# SCH.net
KiCad netlist of a schematic drawn in Altium Designer
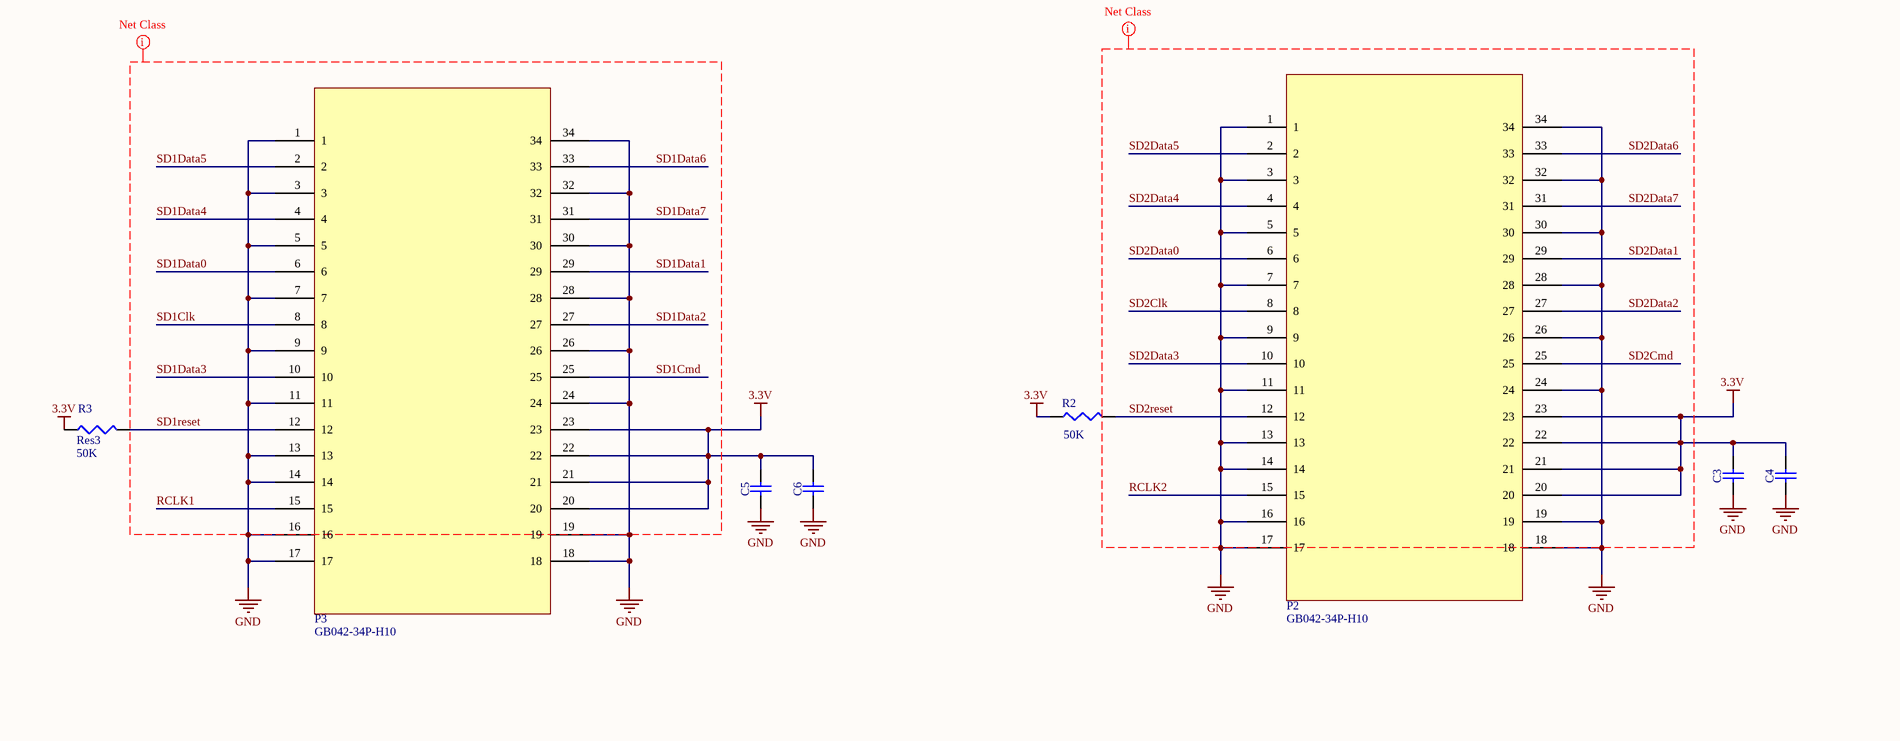
[diagram p0: SCH.SchDoc, top left]
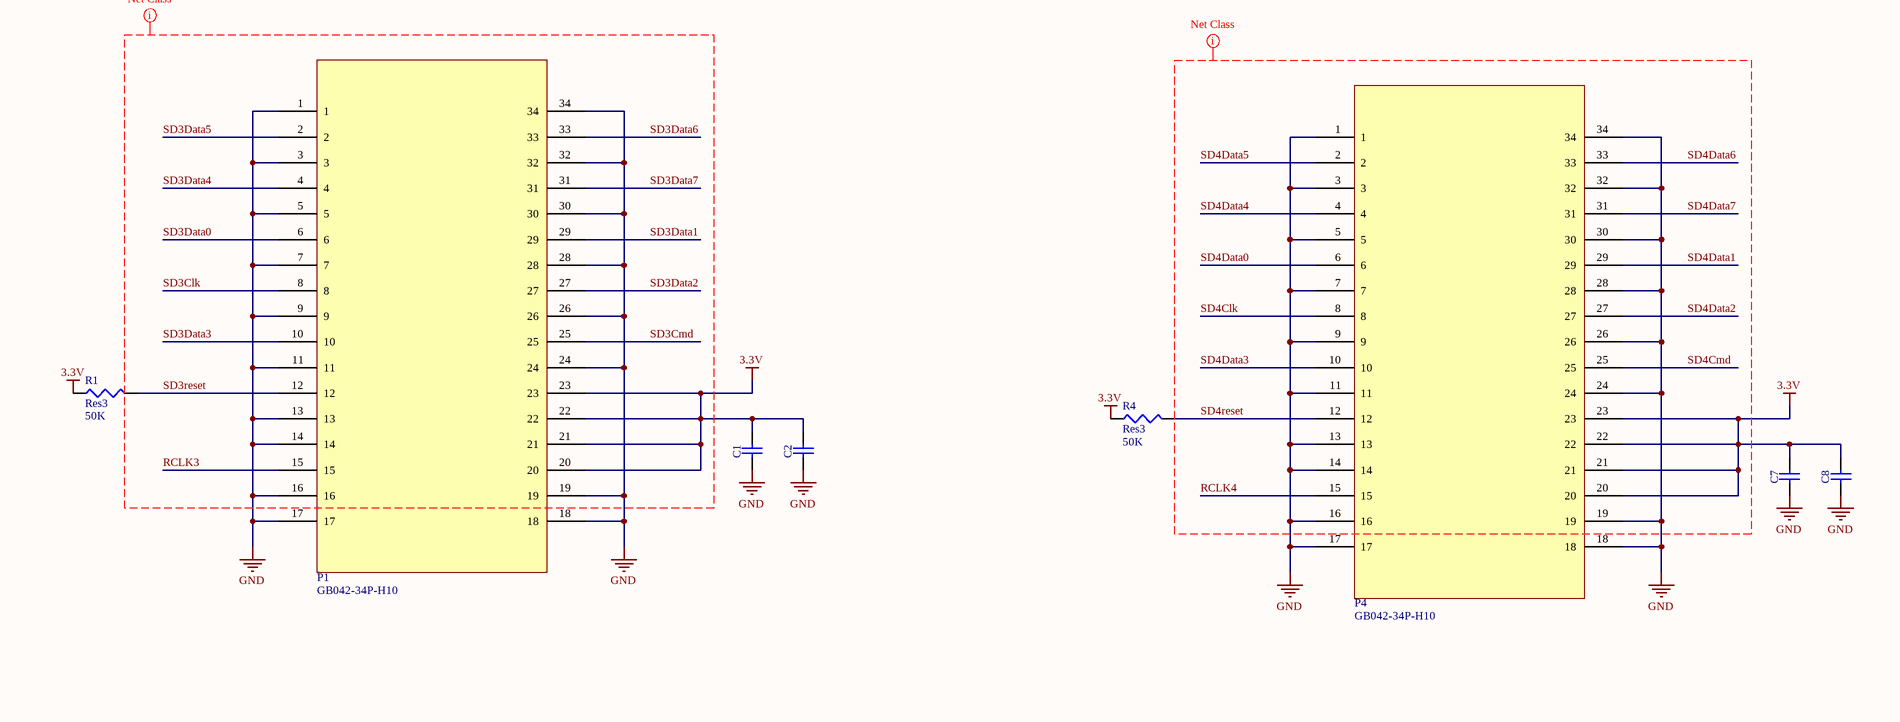
[diagram p1: SCH.SchDoc, top right]
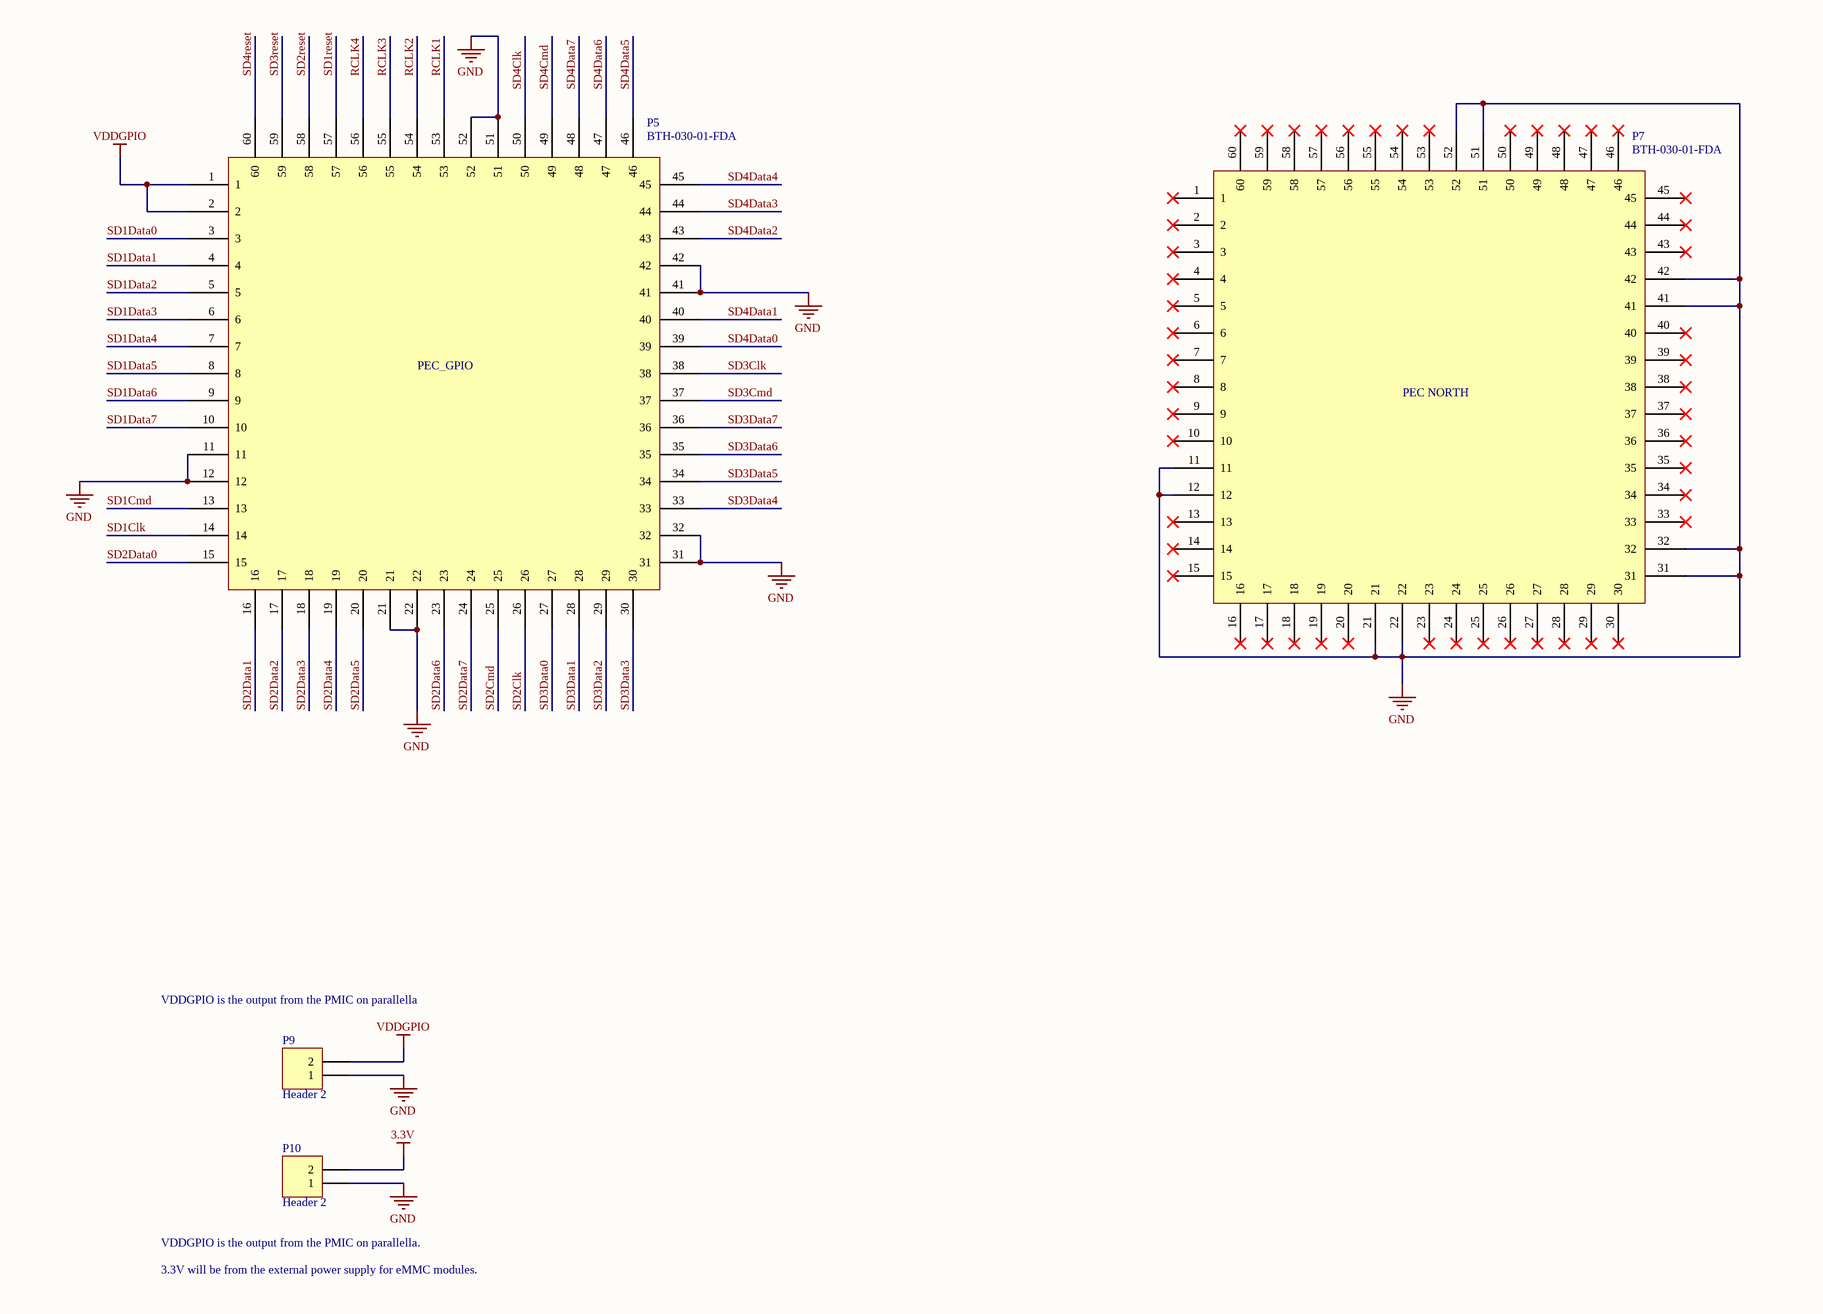
[diagram p2: SCH.SchDoc, bottom left]
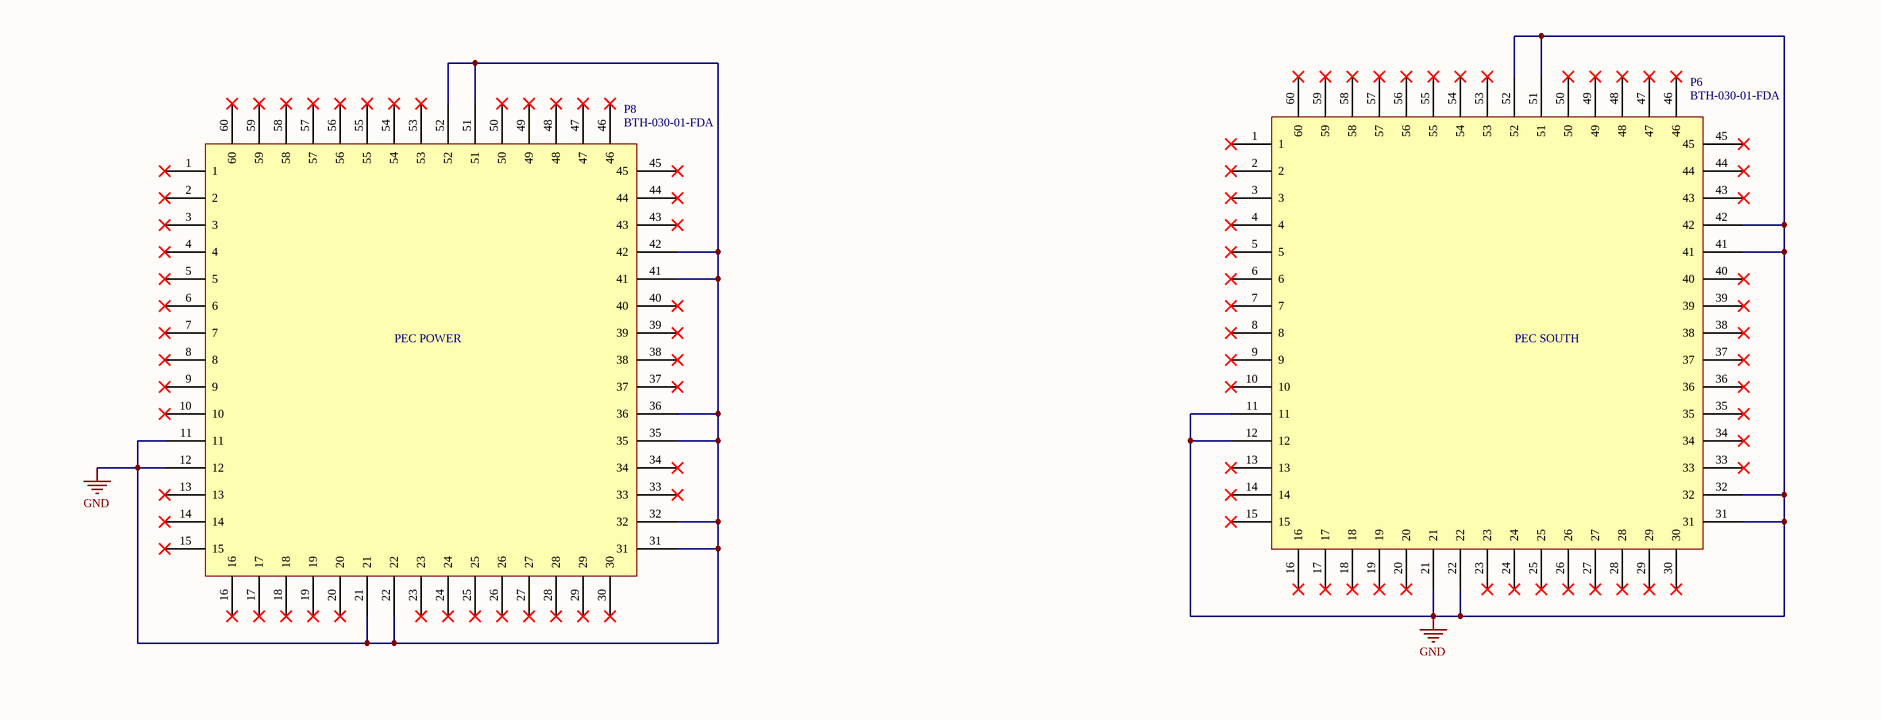
[diagram p3: SCH.SchDoc, bottom right]

(export (version "E")
  (design (tool "Eeschema 10.0.6"))
  (components
    (comp (ref "C1")
      (value "4.7uF")
      (footprint "CAPC3216X140N")
      (description "Non-polarised capacitor")
      (fields
        (field (name "PART NUMBER") "CC1206_4.7UF_16V_10%_X5R")
        (field (name "VOLTAGE") "16V")
        (field (name "AUTHOR") "CERN DEM JLC")
      )
      (libsource (lib "Capacitors") (part "Capacitor - non polarized"))
    )
    (comp (ref "C2")
      (value "100nF")
      (footprint "CAPC1608X87N")
      (description "Non-polarised capacitor")
      (fields
        (field (name "PART NUMBER") "CC0603_100NF_50V_10%_X7R")
        (field (name "VOLTAGE") "50V")
        (field (name "AUTHOR") "CERN DEM JLC")
      )
      (libsource (lib "Capacitors") (part "Capacitor - non polarized"))
    )
    (comp (ref "C3")
      (value "4.7uF")
      (footprint "CAPC3216X140N")
      (description "Non-polarised capacitor")
      (fields
        (field (name "PART NUMBER") "CC1206_4.7UF_16V_10%_X5R")
        (field (name "VOLTAGE") "16V")
        (field (name "AUTHOR") "CERN DEM JLC")
      )
      (libsource (lib "Capacitors") (part "Capacitor - non polarized"))
    )
    (comp (ref "C4")
      (value "100nF")
      (footprint "CAPC1608X87N")
      (description "Non-polarised capacitor")
      (fields
        (field (name "PART NUMBER") "CC0603_100NF_50V_10%_X7R")
        (field (name "VOLTAGE") "50V")
        (field (name "AUTHOR") "CERN DEM JLC")
      )
      (libsource (lib "Capacitors") (part "Capacitor - non polarized"))
    )
    (comp (ref "C5")
      (value "4.7uF")
      (footprint "CAPC3216X140N")
      (description "Non-polarised capacitor")
      (fields
        (field (name "PART NUMBER") "CC1206_4.7UF_16V_10%_X5R")
        (field (name "VOLTAGE") "16V")
        (field (name "AUTHOR") "CERN DEM JLC")
      )
      (libsource (lib "Capacitors") (part "Capacitor - non polarized"))
    )
    (comp (ref "C6")
      (value "100nF")
      (footprint "CAPC1608X87N")
      (description "Non-polarised capacitor")
      (fields
        (field (name "PART NUMBER") "CC0603_100NF_50V_10%_X7R")
        (field (name "VOLTAGE") "50V")
        (field (name "AUTHOR") "CERN DEM JLC")
      )
      (libsource (lib "Capacitors") (part "Capacitor - non polarized"))
    )
    (comp (ref "C7")
      (value "4.7uF")
      (footprint "CAPC3216X140N")
      (description "Non-polarised capacitor")
      (fields
        (field (name "PART NUMBER") "CC1206_4.7UF_16V_10%_X5R")
        (field (name "VOLTAGE") "16V")
        (field (name "AUTHOR") "CERN DEM JLC")
      )
      (libsource (lib "Capacitors") (part "Capacitor - non polarized"))
    )
    (comp (ref "C8")
      (value "100nF")
      (footprint "CAPC1608X87N")
      (description "Non-polarised capacitor")
      (fields
        (field (name "PART NUMBER") "CC0603_100NF_50V_10%_X7R")
        (field (name "VOLTAGE") "50V")
        (field (name "AUTHOR") "CERN DEM JLC")
      )
      (libsource (lib "Capacitors") (part "Capacitor - non polarized"))
    )
    (comp (ref "P1")
      (value "GB042-34P-H10")
      (footprint "GB042-34P-H10")
      (libsource (lib "Schlib1") (part "GB042-34P-H10"))
    )
    (comp (ref "P2")
      (value "GB042-34P-H10")
      (footprint "GB042-34P-H10")
      (libsource (lib "Schlib1") (part "GB042-34P-H10"))
    )
    (comp (ref "P3")
      (value "GB042-34P-H10")
      (footprint "GB042-34P-H10")
      (libsource (lib "Schlib1") (part "GB042-34P-H10"))
    )
    (comp (ref "P4")
      (value "GB042-34P-H10")
      (footprint "GB042-34P-H10")
      (libsource (lib "Schlib1") (part "GB042-34P-H10"))
    )
    (comp (ref "P5")
      (value "BTH-030-01-FDA")
      (footprint "BTH-030-01-F-D-A")
      (libsource (lib "Schlib1") (part "BTH-030-01-FDA"))
    )
    (comp (ref "P6")
      (value "BTH-030-01-FDA")
      (footprint "BTH-030-01-F-D-A")
      (libsource (lib "Schlib1") (part "BTH-030-01-FDA"))
    )
    (comp (ref "P7")
      (value "BTH-030-01-FDA")
      (footprint "BTH-030-01-F-D-A")
      (libsource (lib "Schlib1") (part "BTH-030-01-FDA"))
    )
    (comp (ref "P8")
      (value "BTH-030-01-FDA")
      (footprint "BTH-030-01-F-D-A")
      (libsource (lib "Schlib1") (part "BTH-030-01-FDA"))
    )
    (comp (ref "P9")
      (value "Header 2")
      (footprint "HDR1X2")
      (description "Header, 2-Pin")
      (fields (field (name "PUBLISHER") "Altium Limited"))
      (libsource (lib "Miscellaneous Connectors") (part "Header 2"))
    )
    (comp (ref "P10")
      (value "Header 2")
      (footprint "HDR1X2")
      (description "Header, 2-Pin")
      (fields (field (name "PUBLISHER") "Altium Limited"))
      (libsource (lib "Miscellaneous Connectors") (part "Header 2"))
    )
    (comp (ref "R1")
      (value "Res3")
      (footprint "J1-0603")
      (description "Resistor")
      (fields (field (name "ALTIUM_VALUE") "50K") (field (name "PUBLISHER") "Altium Limited"))
      (libsource (lib "Miscellaneous Devices") (part "Res3"))
    )
    (comp (ref "R2")
      (value "50K")
      (footprint "J1-0603")
      (description "Resistor")
      (fields (field (name "Comment") "Res3") (field (name "PUBLISHER") "Altium Limited"))
      (libsource (lib "Miscellaneous Devices") (part "Res3"))
    )
    (comp (ref "R3")
      (value "Res3")
      (footprint "J1-0603")
      (description "Resistor")
      (fields (field (name "ALTIUM_VALUE") "50K") (field (name "PUBLISHER") "Altium Limited"))
      (libsource (lib "Miscellaneous Devices") (part "Res3"))
    )
    (comp (ref "R4")
      (value "Res3")
      (footprint "J1-0603")
      (description "Resistor")
      (fields (field (name "ALTIUM_VALUE") "50K") (field (name "PUBLISHER") "Altium Limited"))
      (libsource (lib "Miscellaneous Devices") (part "Res3"))
    )
  )
  (nets
    (net (code "1") (name "/RCLK1") (class "Default")
      (node (ref "P3") (pin "15") (pinfunction "15_15") (pintype "passive"))
      (node (ref "P5") (pin "53") (pinfunction "53_53") (pintype "passive"))
    )
    (net (code "2") (name "/RCLK2") (class "Default")
      (node (ref "P2") (pin "15") (pinfunction "15_15") (pintype "passive"))
      (node (ref "P5") (pin "54") (pinfunction "54_54") (pintype "passive"))
    )
    (net (code "3") (name "/RCLK3") (class "Default")
      (node (ref "P1") (pin "15") (pinfunction "15_15") (pintype "passive"))
      (node (ref "P5") (pin "55") (pinfunction "55_55") (pintype "passive"))
    )
    (net (code "4") (name "/RCLK4") (class "Default")
      (node (ref "P4") (pin "15") (pinfunction "15_15") (pintype "passive"))
      (node (ref "P5") (pin "56") (pinfunction "56_56") (pintype "passive"))
    )
    (net (code "5") (name "/SD1Clk") (class "Default")
      (node (ref "P3") (pin "8") (pinfunction "8_8") (pintype "passive"))
      (node (ref "P5") (pin "14") (pinfunction "14_14") (pintype "passive"))
    )
    (net (code "6") (name "/SD1Cmd") (class "Default")
      (node (ref "P3") (pin "25") (pinfunction "25_25") (pintype "passive"))
      (node (ref "P5") (pin "13") (pinfunction "13_13") (pintype "passive"))
    )
    (net (code "7") (name "/SD1Data0") (class "Default")
      (node (ref "P3") (pin "6") (pinfunction "6_6") (pintype "passive"))
      (node (ref "P5") (pin "3") (pinfunction "3_3") (pintype "passive"))
    )
    (net (code "8") (name "/SD1Data1") (class "Default")
      (node (ref "P3") (pin "29") (pinfunction "29_29") (pintype "passive"))
      (node (ref "P5") (pin "4") (pinfunction "4_4") (pintype "passive"))
    )
    (net (code "9") (name "/SD1Data2") (class "Default")
      (node (ref "P3") (pin "27") (pinfunction "27_27") (pintype "passive"))
      (node (ref "P5") (pin "5") (pinfunction "5_5") (pintype "passive"))
    )
    (net (code "10") (name "/SD1Data3") (class "Default")
      (node (ref "P3") (pin "10") (pinfunction "10_10") (pintype "passive"))
      (node (ref "P5") (pin "6") (pinfunction "6_6") (pintype "passive"))
    )
    (net (code "11") (name "/SD1Data4") (class "Default")
      (node (ref "P3") (pin "4") (pinfunction "4_4") (pintype "passive"))
      (node (ref "P5") (pin "7") (pinfunction "7_7") (pintype "passive"))
    )
    (net (code "12") (name "/SD1Data5") (class "Default")
      (node (ref "P3") (pin "2") (pinfunction "2_2") (pintype "passive"))
      (node (ref "P5") (pin "8") (pinfunction "8_8") (pintype "passive"))
    )
    (net (code "13") (name "/SD1Data6") (class "Default")
      (node (ref "P3") (pin "33") (pinfunction "33_33") (pintype "passive"))
      (node (ref "P5") (pin "9") (pinfunction "9_9") (pintype "passive"))
    )
    (net (code "14") (name "/SD1Data7") (class "Default")
      (node (ref "P3") (pin "31") (pinfunction "31_31") (pintype "passive"))
      (node (ref "P5") (pin "10") (pinfunction "10_10") (pintype "passive"))
    )
    (net (code "15") (name "/SD1reset") (class "Default")
      (node (ref "P3") (pin "12") (pinfunction "12_12") (pintype "passive"))
      (node (ref "P5") (pin "57") (pinfunction "57_57") (pintype "passive"))
      (node (ref "R3") (pin "2") (pinfunction "2_2") (pintype "passive"))
    )
    (net (code "16") (name "/SD2Clk") (class "Default")
      (node (ref "P2") (pin "8") (pinfunction "8_8") (pintype "passive"))
      (node (ref "P5") (pin "26") (pinfunction "26_26") (pintype "passive"))
    )
    (net (code "17") (name "/SD2Cmd") (class "Default")
      (node (ref "P2") (pin "25") (pinfunction "25_25") (pintype "passive"))
      (node (ref "P5") (pin "25") (pinfunction "25_25") (pintype "passive"))
    )
    (net (code "18") (name "/SD2Data0") (class "Default")
      (node (ref "P2") (pin "6") (pinfunction "6_6") (pintype "passive"))
      (node (ref "P5") (pin "15") (pinfunction "15_15") (pintype "passive"))
    )
    (net (code "19") (name "/SD2Data1") (class "Default")
      (node (ref "P2") (pin "29") (pinfunction "29_29") (pintype "passive"))
      (node (ref "P5") (pin "16") (pinfunction "16_16") (pintype "passive"))
    )
    (net (code "20") (name "/SD2Data2") (class "Default")
      (node (ref "P2") (pin "27") (pinfunction "27_27") (pintype "passive"))
      (node (ref "P5") (pin "17") (pinfunction "17_17") (pintype "passive"))
    )
    (net (code "21") (name "/SD2Data3") (class "Default")
      (node (ref "P2") (pin "10") (pinfunction "10_10") (pintype "passive"))
      (node (ref "P5") (pin "18") (pinfunction "18_18") (pintype "passive"))
    )
    (net (code "22") (name "/SD2Data4") (class "Default")
      (node (ref "P2") (pin "4") (pinfunction "4_4") (pintype "passive"))
      (node (ref "P5") (pin "19") (pinfunction "19_19") (pintype "passive"))
    )
    (net (code "23") (name "/SD2Data5") (class "Default")
      (node (ref "P2") (pin "2") (pinfunction "2_2") (pintype "passive"))
      (node (ref "P5") (pin "20") (pinfunction "20_20") (pintype "passive"))
    )
    (net (code "24") (name "/SD2Data6") (class "Default")
      (node (ref "P2") (pin "33") (pinfunction "33_33") (pintype "passive"))
      (node (ref "P5") (pin "23") (pinfunction "23_23") (pintype "passive"))
    )
    (net (code "25") (name "/SD2Data7") (class "Default")
      (node (ref "P2") (pin "31") (pinfunction "31_31") (pintype "passive"))
      (node (ref "P5") (pin "24") (pinfunction "24_24") (pintype "passive"))
    )
    (net (code "26") (name "/SD2reset") (class "Default")
      (node (ref "P2") (pin "12") (pinfunction "12_12") (pintype "passive"))
      (node (ref "P5") (pin "58") (pinfunction "58_58") (pintype "passive"))
      (node (ref "R2") (pin "2") (pinfunction "2_2") (pintype "passive"))
    )
    (net (code "27") (name "/SD3Clk") (class "Default")
      (node (ref "P1") (pin "8") (pinfunction "8_8") (pintype "passive"))
      (node (ref "P5") (pin "38") (pinfunction "38_38") (pintype "passive"))
    )
    (net (code "28") (name "/SD3Cmd") (class "Default")
      (node (ref "P1") (pin "25") (pinfunction "25_25") (pintype "passive"))
      (node (ref "P5") (pin "37") (pinfunction "37_37") (pintype "passive"))
    )
    (net (code "29") (name "/SD3Data0") (class "Default")
      (node (ref "P1") (pin "6") (pinfunction "6_6") (pintype "passive"))
      (node (ref "P5") (pin "27") (pinfunction "27_27") (pintype "passive"))
    )
    (net (code "30") (name "/SD3Data1") (class "Default")
      (node (ref "P1") (pin "29") (pinfunction "29_29") (pintype "passive"))
      (node (ref "P5") (pin "28") (pinfunction "28_28") (pintype "passive"))
    )
    (net (code "31") (name "/SD3Data2") (class "Default")
      (node (ref "P1") (pin "27") (pinfunction "27_27") (pintype "passive"))
      (node (ref "P5") (pin "29") (pinfunction "29_29") (pintype "passive"))
    )
    (net (code "32") (name "/SD3Data3") (class "Default")
      (node (ref "P1") (pin "10") (pinfunction "10_10") (pintype "passive"))
      (node (ref "P5") (pin "30") (pinfunction "30_30") (pintype "passive"))
    )
    (net (code "33") (name "/SD3Data4") (class "Default")
      (node (ref "P1") (pin "4") (pinfunction "4_4") (pintype "passive"))
      (node (ref "P5") (pin "33") (pinfunction "33_33") (pintype "passive"))
    )
    (net (code "34") (name "/SD3Data5") (class "Default")
      (node (ref "P1") (pin "2") (pinfunction "2_2") (pintype "passive"))
      (node (ref "P5") (pin "34") (pinfunction "34_34") (pintype "passive"))
    )
    (net (code "35") (name "/SD3Data6") (class "Default")
      (node (ref "P1") (pin "33") (pinfunction "33_33") (pintype "passive"))
      (node (ref "P5") (pin "35") (pinfunction "35_35") (pintype "passive"))
    )
    (net (code "36") (name "/SD3Data7") (class "Default")
      (node (ref "P1") (pin "31") (pinfunction "31_31") (pintype "passive"))
      (node (ref "P5") (pin "36") (pinfunction "36_36") (pintype "passive"))
    )
    (net (code "37") (name "/SD3reset") (class "Default")
      (node (ref "P1") (pin "12") (pinfunction "12_12") (pintype "passive"))
      (node (ref "P5") (pin "59") (pinfunction "59_59") (pintype "passive"))
      (node (ref "R1") (pin "2") (pinfunction "2_2") (pintype "passive"))
    )
    (net (code "38") (name "/SD4Clk") (class "Default")
      (node (ref "P4") (pin "8") (pinfunction "8_8") (pintype "passive"))
      (node (ref "P5") (pin "50") (pinfunction "50_50") (pintype "passive"))
    )
    (net (code "39") (name "/SD4Cmd") (class "Default")
      (node (ref "P4") (pin "25") (pinfunction "25_25") (pintype "passive"))
      (node (ref "P5") (pin "49") (pinfunction "49_49") (pintype "passive"))
    )
    (net (code "40") (name "/SD4Data0") (class "Default")
      (node (ref "P4") (pin "6") (pinfunction "6_6") (pintype "passive"))
      (node (ref "P5") (pin "39") (pinfunction "39_39") (pintype "passive"))
    )
    (net (code "41") (name "/SD4Data1") (class "Default")
      (node (ref "P4") (pin "29") (pinfunction "29_29") (pintype "passive"))
      (node (ref "P5") (pin "40") (pinfunction "40_40") (pintype "passive"))
    )
    (net (code "42") (name "/SD4Data2") (class "Default")
      (node (ref "P4") (pin "27") (pinfunction "27_27") (pintype "passive"))
      (node (ref "P5") (pin "43") (pinfunction "43_43") (pintype "passive"))
    )
    (net (code "43") (name "/SD4Data3") (class "Default")
      (node (ref "P4") (pin "10") (pinfunction "10_10") (pintype "passive"))
      (node (ref "P5") (pin "44") (pinfunction "44_44") (pintype "passive"))
    )
    (net (code "44") (name "/SD4Data4") (class "Default")
      (node (ref "P4") (pin "4") (pinfunction "4_4") (pintype "passive"))
      (node (ref "P5") (pin "45") (pinfunction "45_45") (pintype "passive"))
    )
    (net (code "45") (name "/SD4Data5") (class "Default")
      (node (ref "P4") (pin "2") (pinfunction "2_2") (pintype "passive"))
      (node (ref "P5") (pin "46") (pinfunction "46_46") (pintype "passive"))
    )
    (net (code "46") (name "/SD4Data6") (class "Default")
      (node (ref "P4") (pin "33") (pinfunction "33_33") (pintype "passive"))
      (node (ref "P5") (pin "47") (pinfunction "47_47") (pintype "passive"))
    )
    (net (code "47") (name "/SD4Data7") (class "Default")
      (node (ref "P4") (pin "31") (pinfunction "31_31") (pintype "passive"))
      (node (ref "P5") (pin "48") (pinfunction "48_48") (pintype "passive"))
    )
    (net (code "48") (name "/SD4reset") (class "Default")
      (node (ref "P4") (pin "12") (pinfunction "12_12") (pintype "passive"))
      (node (ref "P5") (pin "60") (pinfunction "60_60") (pintype "passive"))
      (node (ref "R4") (pin "2") (pinfunction "2_2") (pintype "passive"))
    )
    (net (code "49") (name "3.3V") (class "Default")
      (node (ref "C1") (pin "2") (pinfunction "2_2") (pintype "passive"))
      (node (ref "C2") (pin "2") (pinfunction "2_2") (pintype "passive"))
      (node (ref "C3") (pin "2") (pinfunction "2_2") (pintype "passive"))
      (node (ref "C4") (pin "2") (pinfunction "2_2") (pintype "passive"))
      (node (ref "C5") (pin "2") (pinfunction "2_2") (pintype "passive"))
      (node (ref "C6") (pin "2") (pinfunction "2_2") (pintype "passive"))
      (node (ref "C7") (pin "2") (pinfunction "2_2") (pintype "passive"))
      (node (ref "C8") (pin "2") (pinfunction "2_2") (pintype "passive"))
      (node (ref "P1") (pin "20") (pinfunction "20_20") (pintype "passive"))
      (node (ref "P1") (pin "21") (pinfunction "21_21") (pintype "passive"))
      (node (ref "P1") (pin "22") (pinfunction "22_22") (pintype "passive"))
      (node (ref "P1") (pin "23") (pinfunction "23_23") (pintype "passive"))
      (node (ref "P10") (pin "2") (pinfunction "2_2") (pintype "passive"))
      (node (ref "P2") (pin "20") (pinfunction "20_20") (pintype "passive"))
      (node (ref "P2") (pin "21") (pinfunction "21_21") (pintype "passive"))
      (node (ref "P2") (pin "22") (pinfunction "22_22") (pintype "passive"))
      (node (ref "P2") (pin "23") (pinfunction "23_23") (pintype "passive"))
      (node (ref "P3") (pin "20") (pinfunction "20_20") (pintype "passive"))
      (node (ref "P3") (pin "21") (pinfunction "21_21") (pintype "passive"))
      (node (ref "P3") (pin "22") (pinfunction "22_22") (pintype "passive"))
      (node (ref "P3") (pin "23") (pinfunction "23_23") (pintype "passive"))
      (node (ref "P4") (pin "20") (pinfunction "20_20") (pintype "passive"))
      (node (ref "P4") (pin "21") (pinfunction "21_21") (pintype "passive"))
      (node (ref "P4") (pin "22") (pinfunction "22_22") (pintype "passive"))
      (node (ref "P4") (pin "23") (pinfunction "23_23") (pintype "passive"))
      (node (ref "R1") (pin "1") (pinfunction "1_1") (pintype "passive"))
      (node (ref "R2") (pin "1") (pinfunction "1_1") (pintype "passive"))
      (node (ref "R3") (pin "1") (pinfunction "1_1") (pintype "passive"))
      (node (ref "R4") (pin "1") (pinfunction "1_1") (pintype "passive"))
    )
    (net (code "50") (name "GND") (class "Default")
      (node (ref "C1") (pin "1") (pinfunction "1_1") (pintype "passive"))
      (node (ref "C2") (pin "1") (pinfunction "1_1") (pintype "passive"))
      (node (ref "C3") (pin "1") (pinfunction "1_1") (pintype "passive"))
      (node (ref "C4") (pin "1") (pinfunction "1_1") (pintype "passive"))
      (node (ref "C5") (pin "1") (pinfunction "1_1") (pintype "passive"))
      (node (ref "C6") (pin "1") (pinfunction "1_1") (pintype "passive"))
      (node (ref "C7") (pin "1") (pinfunction "1_1") (pintype "passive"))
      (node (ref "C8") (pin "1") (pinfunction "1_1") (pintype "passive"))
      (node (ref "P1") (pin "1") (pinfunction "1_1") (pintype "passive"))
      (node (ref "P1") (pin "11") (pinfunction "11_11") (pintype "passive"))
      (node (ref "P1") (pin "13") (pinfunction "13_13") (pintype "passive"))
      (node (ref "P1") (pin "14") (pinfunction "14_14") (pintype "passive"))
      (node (ref "P1") (pin "16") (pinfunction "16_16") (pintype "passive"))
      (node (ref "P1") (pin "17") (pinfunction "17_17") (pintype "passive"))
      (node (ref "P1") (pin "18") (pinfunction "18_18") (pintype "passive"))
      (node (ref "P1") (pin "19") (pinfunction "19_19") (pintype "passive"))
      (node (ref "P1") (pin "24") (pinfunction "24_24") (pintype "passive"))
      (node (ref "P1") (pin "26") (pinfunction "26_26") (pintype "passive"))
      (node (ref "P1") (pin "28") (pinfunction "28_28") (pintype "passive"))
      (node (ref "P1") (pin "3") (pinfunction "3_3") (pintype "passive"))
      (node (ref "P1") (pin "30") (pinfunction "30_30") (pintype "passive"))
      (node (ref "P1") (pin "32") (pinfunction "32_32") (pintype "passive"))
      (node (ref "P1") (pin "34") (pinfunction "34_34") (pintype "passive"))
      (node (ref "P1") (pin "5") (pinfunction "5_5") (pintype "passive"))
      (node (ref "P1") (pin "7") (pinfunction "7_7") (pintype "passive"))
      (node (ref "P1") (pin "9") (pinfunction "9_9") (pintype "passive"))
      (node (ref "P10") (pin "1") (pinfunction "1_1") (pintype "passive"))
      (node (ref "P2") (pin "1") (pinfunction "1_1") (pintype "passive"))
      (node (ref "P2") (pin "11") (pinfunction "11_11") (pintype "passive"))
      (node (ref "P2") (pin "13") (pinfunction "13_13") (pintype "passive"))
      (node (ref "P2") (pin "14") (pinfunction "14_14") (pintype "passive"))
      (node (ref "P2") (pin "16") (pinfunction "16_16") (pintype "passive"))
      (node (ref "P2") (pin "17") (pinfunction "17_17") (pintype "passive"))
      (node (ref "P2") (pin "18") (pinfunction "18_18") (pintype "passive"))
      (node (ref "P2") (pin "19") (pinfunction "19_19") (pintype "passive"))
      (node (ref "P2") (pin "24") (pinfunction "24_24") (pintype "passive"))
      (node (ref "P2") (pin "26") (pinfunction "26_26") (pintype "passive"))
      (node (ref "P2") (pin "28") (pinfunction "28_28") (pintype "passive"))
      (node (ref "P2") (pin "3") (pinfunction "3_3") (pintype "passive"))
      (node (ref "P2") (pin "30") (pinfunction "30_30") (pintype "passive"))
      (node (ref "P2") (pin "32") (pinfunction "32_32") (pintype "passive"))
      (node (ref "P2") (pin "34") (pinfunction "34_34") (pintype "passive"))
      (node (ref "P2") (pin "5") (pinfunction "5_5") (pintype "passive"))
      (node (ref "P2") (pin "7") (pinfunction "7_7") (pintype "passive"))
      (node (ref "P2") (pin "9") (pinfunction "9_9") (pintype "passive"))
      (node (ref "P3") (pin "1") (pinfunction "1_1") (pintype "passive"))
      (node (ref "P3") (pin "11") (pinfunction "11_11") (pintype "passive"))
      (node (ref "P3") (pin "13") (pinfunction "13_13") (pintype "passive"))
      (node (ref "P3") (pin "14") (pinfunction "14_14") (pintype "passive"))
      (node (ref "P3") (pin "16") (pinfunction "16_16") (pintype "passive"))
      (node (ref "P3") (pin "17") (pinfunction "17_17") (pintype "passive"))
      (node (ref "P3") (pin "18") (pinfunction "18_18") (pintype "passive"))
      (node (ref "P3") (pin "19") (pinfunction "19_19") (pintype "passive"))
      (node (ref "P3") (pin "24") (pinfunction "24_24") (pintype "passive"))
      (node (ref "P3") (pin "26") (pinfunction "26_26") (pintype "passive"))
      (node (ref "P3") (pin "28") (pinfunction "28_28") (pintype "passive"))
      (node (ref "P3") (pin "3") (pinfunction "3_3") (pintype "passive"))
      (node (ref "P3") (pin "30") (pinfunction "30_30") (pintype "passive"))
      (node (ref "P3") (pin "32") (pinfunction "32_32") (pintype "passive"))
      (node (ref "P3") (pin "34") (pinfunction "34_34") (pintype "passive"))
      (node (ref "P3") (pin "5") (pinfunction "5_5") (pintype "passive"))
      (node (ref "P3") (pin "7") (pinfunction "7_7") (pintype "passive"))
      (node (ref "P3") (pin "9") (pinfunction "9_9") (pintype "passive"))
      (node (ref "P4") (pin "1") (pinfunction "1_1") (pintype "passive"))
      (node (ref "P4") (pin "11") (pinfunction "11_11") (pintype "passive"))
      (node (ref "P4") (pin "13") (pinfunction "13_13") (pintype "passive"))
      (node (ref "P4") (pin "14") (pinfunction "14_14") (pintype "passive"))
      (node (ref "P4") (pin "16") (pinfunction "16_16") (pintype "passive"))
      (node (ref "P4") (pin "17") (pinfunction "17_17") (pintype "passive"))
      (node (ref "P4") (pin "18") (pinfunction "18_18") (pintype "passive"))
      (node (ref "P4") (pin "19") (pinfunction "19_19") (pintype "passive"))
      (node (ref "P4") (pin "24") (pinfunction "24_24") (pintype "passive"))
      (node (ref "P4") (pin "26") (pinfunction "26_26") (pintype "passive"))
      (node (ref "P4") (pin "28") (pinfunction "28_28") (pintype "passive"))
      (node (ref "P4") (pin "3") (pinfunction "3_3") (pintype "passive"))
      (node (ref "P4") (pin "30") (pinfunction "30_30") (pintype "passive"))
      (node (ref "P4") (pin "32") (pinfunction "32_32") (pintype "passive"))
      (node (ref "P4") (pin "34") (pinfunction "34_34") (pintype "passive"))
      (node (ref "P4") (pin "5") (pinfunction "5_5") (pintype "passive"))
      (node (ref "P4") (pin "7") (pinfunction "7_7") (pintype "passive"))
      (node (ref "P4") (pin "9") (pinfunction "9_9") (pintype "passive"))
      (node (ref "P5") (pin "11") (pinfunction "11_11") (pintype "passive"))
      (node (ref "P5") (pin "12") (pinfunction "12_12") (pintype "passive"))
      (node (ref "P5") (pin "21") (pinfunction "21_21") (pintype "passive"))
      (node (ref "P5") (pin "22") (pinfunction "22_22") (pintype "passive"))
      (node (ref "P5") (pin "31") (pinfunction "31_31") (pintype "passive"))
      (node (ref "P5") (pin "32") (pinfunction "32_32") (pintype "passive"))
      (node (ref "P5") (pin "41") (pinfunction "41_41") (pintype "passive"))
      (node (ref "P5") (pin "42") (pinfunction "42_42") (pintype "passive"))
      (node (ref "P5") (pin "51") (pinfunction "51_51") (pintype "passive"))
      (node (ref "P5") (pin "52") (pinfunction "52_52") (pintype "passive"))
      (node (ref "P6") (pin "11") (pinfunction "11_11") (pintype "passive"))
      (node (ref "P6") (pin "12") (pinfunction "12_12") (pintype "passive"))
      (node (ref "P6") (pin "21") (pinfunction "21_21") (pintype "passive"))
      (node (ref "P6") (pin "22") (pinfunction "22_22") (pintype "passive"))
      (node (ref "P6") (pin "31") (pinfunction "31_31") (pintype "passive"))
      (node (ref "P6") (pin "32") (pinfunction "32_32") (pintype "passive"))
      (node (ref "P6") (pin "41") (pinfunction "41_41") (pintype "passive"))
      (node (ref "P6") (pin "42") (pinfunction "42_42") (pintype "passive"))
      (node (ref "P6") (pin "51") (pinfunction "51_51") (pintype "passive"))
      (node (ref "P6") (pin "52") (pinfunction "52_52") (pintype "passive"))
      (node (ref "P7") (pin "11") (pinfunction "11_11") (pintype "passive"))
      (node (ref "P7") (pin "12") (pinfunction "12_12") (pintype "passive"))
      (node (ref "P7") (pin "21") (pinfunction "21_21") (pintype "passive"))
      (node (ref "P7") (pin "22") (pinfunction "22_22") (pintype "passive"))
      (node (ref "P7") (pin "31") (pinfunction "31_31") (pintype "passive"))
      (node (ref "P7") (pin "32") (pinfunction "32_32") (pintype "passive"))
      (node (ref "P7") (pin "41") (pinfunction "41_41") (pintype "passive"))
      (node (ref "P7") (pin "42") (pinfunction "42_42") (pintype "passive"))
      (node (ref "P7") (pin "51") (pinfunction "51_51") (pintype "passive"))
      (node (ref "P7") (pin "52") (pinfunction "52_52") (pintype "passive"))
      (node (ref "P8") (pin "11") (pinfunction "11_11") (pintype "passive"))
      (node (ref "P8") (pin "12") (pinfunction "12_12") (pintype "passive"))
      (node (ref "P8") (pin "21") (pinfunction "21_21") (pintype "passive"))
      (node (ref "P8") (pin "22") (pinfunction "22_22") (pintype "passive"))
      (node (ref "P8") (pin "31") (pinfunction "31_31") (pintype "passive"))
      (node (ref "P8") (pin "32") (pinfunction "32_32") (pintype "passive"))
      (node (ref "P8") (pin "35") (pinfunction "35_35") (pintype "passive"))
      (node (ref "P8") (pin "36") (pinfunction "36_36") (pintype "passive"))
      (node (ref "P8") (pin "41") (pinfunction "41_41") (pintype "passive"))
      (node (ref "P8") (pin "42") (pinfunction "42_42") (pintype "passive"))
      (node (ref "P8") (pin "51") (pinfunction "51_51") (pintype "passive"))
      (node (ref "P8") (pin "52") (pinfunction "52_52") (pintype "passive"))
      (node (ref "P9") (pin "1") (pinfunction "1_1") (pintype "passive"))
    )
    (net (code "51") (name "VDDGPIO") (class "Default")
      (node (ref "P5") (pin "1") (pinfunction "1_1") (pintype "passive"))
      (node (ref "P5") (pin "2") (pinfunction "2_2") (pintype "passive"))
      (node (ref "P9") (pin "2") (pinfunction "2_2") (pintype "passive"))
    )
    (net (code "52") (name "unconnected-(P6-Pad1)") (class "Default")
      (node (ref "P6") (pin "1") (pinfunction "1_1") (pintype "passive+no_connect"))
    )
    (net (code "53") (name "unconnected-(P6-Pad2)") (class "Default")
      (node (ref "P6") (pin "2") (pinfunction "2_2") (pintype "passive+no_connect"))
    )
    (net (code "54") (name "unconnected-(P6-Pad3)") (class "Default")
      (node (ref "P6") (pin "3") (pinfunction "3_3") (pintype "passive+no_connect"))
    )
    (net (code "55") (name "unconnected-(P6-Pad4)") (class "Default")
      (node (ref "P6") (pin "4") (pinfunction "4_4") (pintype "passive+no_connect"))
    )
    (net (code "56") (name "unconnected-(P6-Pad5)") (class "Default")
      (node (ref "P6") (pin "5") (pinfunction "5_5") (pintype "passive+no_connect"))
    )
    (net (code "57") (name "unconnected-(P6-Pad6)") (class "Default")
      (node (ref "P6") (pin "6") (pinfunction "6_6") (pintype "passive+no_connect"))
    )
    (net (code "58") (name "unconnected-(P6-Pad7)") (class "Default")
      (node (ref "P6") (pin "7") (pinfunction "7_7") (pintype "passive+no_connect"))
    )
    (net (code "59") (name "unconnected-(P6-Pad8)") (class "Default")
      (node (ref "P6") (pin "8") (pinfunction "8_8") (pintype "passive+no_connect"))
    )
    (net (code "60") (name "unconnected-(P6-Pad9)") (class "Default")
      (node (ref "P6") (pin "9") (pinfunction "9_9") (pintype "passive+no_connect"))
    )
    (net (code "61") (name "unconnected-(P6-Pad10)") (class "Default")
      (node (ref "P6") (pin "10") (pinfunction "10_10") (pintype "passive+no_connect"))
    )
    (net (code "62") (name "unconnected-(P6-Pad13)") (class "Default")
      (node (ref "P6") (pin "13") (pinfunction "13_13") (pintype "passive+no_connect"))
    )
    (net (code "63") (name "unconnected-(P6-Pad14)") (class "Default")
      (node (ref "P6") (pin "14") (pinfunction "14_14") (pintype "passive+no_connect"))
    )
    (net (code "64") (name "unconnected-(P6-Pad15)") (class "Default")
      (node (ref "P6") (pin "15") (pinfunction "15_15") (pintype "passive+no_connect"))
    )
    (net (code "65") (name "unconnected-(P6-Pad16)") (class "Default")
      (node (ref "P6") (pin "16") (pinfunction "16_16") (pintype "passive+no_connect"))
    )
    (net (code "66") (name "unconnected-(P6-Pad17)") (class "Default")
      (node (ref "P6") (pin "17") (pinfunction "17_17") (pintype "passive+no_connect"))
    )
    (net (code "67") (name "unconnected-(P6-Pad18)") (class "Default")
      (node (ref "P6") (pin "18") (pinfunction "18_18") (pintype "passive+no_connect"))
    )
    (net (code "68") (name "unconnected-(P6-Pad19)") (class "Default")
      (node (ref "P6") (pin "19") (pinfunction "19_19") (pintype "passive+no_connect"))
    )
    (net (code "69") (name "unconnected-(P6-Pad20)") (class "Default")
      (node (ref "P6") (pin "20") (pinfunction "20_20") (pintype "passive+no_connect"))
    )
    (net (code "70") (name "unconnected-(P6-Pad23)") (class "Default")
      (node (ref "P6") (pin "23") (pinfunction "23_23") (pintype "passive+no_connect"))
    )
    (net (code "71") (name "unconnected-(P6-Pad24)") (class "Default")
      (node (ref "P6") (pin "24") (pinfunction "24_24") (pintype "passive+no_connect"))
    )
    (net (code "72") (name "unconnected-(P6-Pad25)") (class "Default")
      (node (ref "P6") (pin "25") (pinfunction "25_25") (pintype "passive+no_connect"))
    )
    (net (code "73") (name "unconnected-(P6-Pad26)") (class "Default")
      (node (ref "P6") (pin "26") (pinfunction "26_26") (pintype "passive+no_connect"))
    )
    (net (code "74") (name "unconnected-(P6-Pad27)") (class "Default")
      (node (ref "P6") (pin "27") (pinfunction "27_27") (pintype "passive+no_connect"))
    )
    (net (code "75") (name "unconnected-(P6-Pad28)") (class "Default")
      (node (ref "P6") (pin "28") (pinfunction "28_28") (pintype "passive+no_connect"))
    )
    (net (code "76") (name "unconnected-(P6-Pad29)") (class "Default")
      (node (ref "P6") (pin "29") (pinfunction "29_29") (pintype "passive+no_connect"))
    )
    (net (code "77") (name "unconnected-(P6-Pad30)") (class "Default")
      (node (ref "P6") (pin "30") (pinfunction "30_30") (pintype "passive+no_connect"))
    )
    (net (code "78") (name "unconnected-(P6-Pad33)") (class "Default")
      (node (ref "P6") (pin "33") (pinfunction "33_33") (pintype "passive+no_connect"))
    )
    (net (code "79") (name "unconnected-(P6-Pad34)") (class "Default")
      (node (ref "P6") (pin "34") (pinfunction "34_34") (pintype "passive+no_connect"))
    )
    (net (code "80") (name "unconnected-(P6-Pad35)") (class "Default")
      (node (ref "P6") (pin "35") (pinfunction "35_35") (pintype "passive+no_connect"))
    )
    (net (code "81") (name "unconnected-(P6-Pad36)") (class "Default")
      (node (ref "P6") (pin "36") (pinfunction "36_36") (pintype "passive+no_connect"))
    )
    (net (code "82") (name "unconnected-(P6-Pad37)") (class "Default")
      (node (ref "P6") (pin "37") (pinfunction "37_37") (pintype "passive+no_connect"))
    )
    (net (code "83") (name "unconnected-(P6-Pad38)") (class "Default")
      (node (ref "P6") (pin "38") (pinfunction "38_38") (pintype "passive+no_connect"))
    )
    (net (code "84") (name "unconnected-(P6-Pad39)") (class "Default")
      (node (ref "P6") (pin "39") (pinfunction "39_39") (pintype "passive+no_connect"))
    )
    (net (code "85") (name "unconnected-(P6-Pad40)") (class "Default")
      (node (ref "P6") (pin "40") (pinfunction "40_40") (pintype "passive+no_connect"))
    )
    (net (code "86") (name "unconnected-(P6-Pad43)") (class "Default")
      (node (ref "P6") (pin "43") (pinfunction "43_43") (pintype "passive+no_connect"))
    )
    (net (code "87") (name "unconnected-(P6-Pad44)") (class "Default")
      (node (ref "P6") (pin "44") (pinfunction "44_44") (pintype "passive+no_connect"))
    )
    (net (code "88") (name "unconnected-(P6-Pad45)") (class "Default")
      (node (ref "P6") (pin "45") (pinfunction "45_45") (pintype "passive+no_connect"))
    )
    (net (code "89") (name "unconnected-(P6-Pad46)") (class "Default")
      (node (ref "P6") (pin "46") (pinfunction "46_46") (pintype "passive+no_connect"))
    )
    (net (code "90") (name "unconnected-(P6-Pad47)") (class "Default")
      (node (ref "P6") (pin "47") (pinfunction "47_47") (pintype "passive+no_connect"))
    )
    (net (code "91") (name "unconnected-(P6-Pad48)") (class "Default")
      (node (ref "P6") (pin "48") (pinfunction "48_48") (pintype "passive+no_connect"))
    )
    (net (code "92") (name "unconnected-(P6-Pad49)") (class "Default")
      (node (ref "P6") (pin "49") (pinfunction "49_49") (pintype "passive+no_connect"))
    )
    (net (code "93") (name "unconnected-(P6-Pad50)") (class "Default")
      (node (ref "P6") (pin "50") (pinfunction "50_50") (pintype "passive+no_connect"))
    )
    (net (code "94") (name "unconnected-(P6-Pad53)") (class "Default")
      (node (ref "P6") (pin "53") (pinfunction "53_53") (pintype "passive+no_connect"))
    )
    (net (code "95") (name "unconnected-(P6-Pad54)") (class "Default")
      (node (ref "P6") (pin "54") (pinfunction "54_54") (pintype "passive+no_connect"))
    )
    (net (code "96") (name "unconnected-(P6-Pad55)") (class "Default")
      (node (ref "P6") (pin "55") (pinfunction "55_55") (pintype "passive+no_connect"))
    )
    (net (code "97") (name "unconnected-(P6-Pad56)") (class "Default")
      (node (ref "P6") (pin "56") (pinfunction "56_56") (pintype "passive+no_connect"))
    )
    (net (code "98") (name "unconnected-(P6-Pad57)") (class "Default")
      (node (ref "P6") (pin "57") (pinfunction "57_57") (pintype "passive+no_connect"))
    )
    (net (code "99") (name "unconnected-(P6-Pad58)") (class "Default")
      (node (ref "P6") (pin "58") (pinfunction "58_58") (pintype "passive+no_connect"))
    )
    (net (code "100") (name "unconnected-(P6-Pad59)") (class "Default")
      (node (ref "P6") (pin "59") (pinfunction "59_59") (pintype "passive+no_connect"))
    )
    (net (code "101") (name "unconnected-(P6-Pad60)") (class "Default")
      (node (ref "P6") (pin "60") (pinfunction "60_60") (pintype "passive+no_connect"))
    )
    (net (code "102") (name "unconnected-(P7-Pad1)") (class "Default")
      (node (ref "P7") (pin "1") (pinfunction "1_1") (pintype "passive+no_connect"))
    )
    (net (code "103") (name "unconnected-(P7-Pad2)") (class "Default")
      (node (ref "P7") (pin "2") (pinfunction "2_2") (pintype "passive+no_connect"))
    )
    (net (code "104") (name "unconnected-(P7-Pad3)") (class "Default")
      (node (ref "P7") (pin "3") (pinfunction "3_3") (pintype "passive+no_connect"))
    )
    (net (code "105") (name "unconnected-(P7-Pad4)") (class "Default")
      (node (ref "P7") (pin "4") (pinfunction "4_4") (pintype "passive+no_connect"))
    )
    (net (code "106") (name "unconnected-(P7-Pad5)") (class "Default")
      (node (ref "P7") (pin "5") (pinfunction "5_5") (pintype "passive+no_connect"))
    )
    (net (code "107") (name "unconnected-(P7-Pad6)") (class "Default")
      (node (ref "P7") (pin "6") (pinfunction "6_6") (pintype "passive+no_connect"))
    )
    (net (code "108") (name "unconnected-(P7-Pad7)") (class "Default")
      (node (ref "P7") (pin "7") (pinfunction "7_7") (pintype "passive+no_connect"))
    )
    (net (code "109") (name "unconnected-(P7-Pad8)") (class "Default")
      (node (ref "P7") (pin "8") (pinfunction "8_8") (pintype "passive+no_connect"))
    )
    (net (code "110") (name "unconnected-(P7-Pad9)") (class "Default")
      (node (ref "P7") (pin "9") (pinfunction "9_9") (pintype "passive+no_connect"))
    )
    (net (code "111") (name "unconnected-(P7-Pad10)") (class "Default")
      (node (ref "P7") (pin "10") (pinfunction "10_10") (pintype "passive+no_connect"))
    )
    (net (code "112") (name "unconnected-(P7-Pad13)") (class "Default")
      (node (ref "P7") (pin "13") (pinfunction "13_13") (pintype "passive+no_connect"))
    )
    (net (code "113") (name "unconnected-(P7-Pad14)") (class "Default")
      (node (ref "P7") (pin "14") (pinfunction "14_14") (pintype "passive+no_connect"))
    )
    (net (code "114") (name "unconnected-(P7-Pad15)") (class "Default")
      (node (ref "P7") (pin "15") (pinfunction "15_15") (pintype "passive+no_connect"))
    )
    (net (code "115") (name "unconnected-(P7-Pad16)") (class "Default")
      (node (ref "P7") (pin "16") (pinfunction "16_16") (pintype "passive+no_connect"))
    )
    (net (code "116") (name "unconnected-(P7-Pad17)") (class "Default")
      (node (ref "P7") (pin "17") (pinfunction "17_17") (pintype "passive+no_connect"))
    )
    (net (code "117") (name "unconnected-(P7-Pad18)") (class "Default")
      (node (ref "P7") (pin "18") (pinfunction "18_18") (pintype "passive+no_connect"))
    )
    (net (code "118") (name "unconnected-(P7-Pad19)") (class "Default")
      (node (ref "P7") (pin "19") (pinfunction "19_19") (pintype "passive+no_connect"))
    )
    (net (code "119") (name "unconnected-(P7-Pad20)") (class "Default")
      (node (ref "P7") (pin "20") (pinfunction "20_20") (pintype "passive+no_connect"))
    )
    (net (code "120") (name "unconnected-(P7-Pad23)") (class "Default")
      (node (ref "P7") (pin "23") (pinfunction "23_23") (pintype "passive+no_connect"))
    )
    (net (code "121") (name "unconnected-(P7-Pad24)") (class "Default")
      (node (ref "P7") (pin "24") (pinfunction "24_24") (pintype "passive+no_connect"))
    )
    (net (code "122") (name "unconnected-(P7-Pad25)") (class "Default")
      (node (ref "P7") (pin "25") (pinfunction "25_25") (pintype "passive+no_connect"))
    )
    (net (code "123") (name "unconnected-(P7-Pad26)") (class "Default")
      (node (ref "P7") (pin "26") (pinfunction "26_26") (pintype "passive+no_connect"))
    )
    (net (code "124") (name "unconnected-(P7-Pad27)") (class "Default")
      (node (ref "P7") (pin "27") (pinfunction "27_27") (pintype "passive+no_connect"))
    )
    (net (code "125") (name "unconnected-(P7-Pad28)") (class "Default")
      (node (ref "P7") (pin "28") (pinfunction "28_28") (pintype "passive+no_connect"))
    )
    (net (code "126") (name "unconnected-(P7-Pad29)") (class "Default")
      (node (ref "P7") (pin "29") (pinfunction "29_29") (pintype "passive+no_connect"))
    )
    (net (code "127") (name "unconnected-(P7-Pad30)") (class "Default")
      (node (ref "P7") (pin "30") (pinfunction "30_30") (pintype "passive+no_connect"))
    )
    (net (code "128") (name "unconnected-(P7-Pad33)") (class "Default")
      (node (ref "P7") (pin "33") (pinfunction "33_33") (pintype "passive+no_connect"))
    )
    (net (code "129") (name "unconnected-(P7-Pad34)") (class "Default")
      (node (ref "P7") (pin "34") (pinfunction "34_34") (pintype "passive+no_connect"))
    )
    (net (code "130") (name "unconnected-(P7-Pad35)") (class "Default")
      (node (ref "P7") (pin "35") (pinfunction "35_35") (pintype "passive+no_connect"))
    )
    (net (code "131") (name "unconnected-(P7-Pad36)") (class "Default")
      (node (ref "P7") (pin "36") (pinfunction "36_36") (pintype "passive+no_connect"))
    )
    (net (code "132") (name "unconnected-(P7-Pad37)") (class "Default")
      (node (ref "P7") (pin "37") (pinfunction "37_37") (pintype "passive+no_connect"))
    )
    (net (code "133") (name "unconnected-(P7-Pad38)") (class "Default")
      (node (ref "P7") (pin "38") (pinfunction "38_38") (pintype "passive+no_connect"))
    )
    (net (code "134") (name "unconnected-(P7-Pad39)") (class "Default")
      (node (ref "P7") (pin "39") (pinfunction "39_39") (pintype "passive+no_connect"))
    )
    (net (code "135") (name "unconnected-(P7-Pad40)") (class "Default")
      (node (ref "P7") (pin "40") (pinfunction "40_40") (pintype "passive+no_connect"))
    )
    (net (code "136") (name "unconnected-(P7-Pad43)") (class "Default")
      (node (ref "P7") (pin "43") (pinfunction "43_43") (pintype "passive+no_connect"))
    )
    (net (code "137") (name "unconnected-(P7-Pad44)") (class "Default")
      (node (ref "P7") (pin "44") (pinfunction "44_44") (pintype "passive+no_connect"))
    )
    (net (code "138") (name "unconnected-(P7-Pad45)") (class "Default")
      (node (ref "P7") (pin "45") (pinfunction "45_45") (pintype "passive+no_connect"))
    )
    (net (code "139") (name "unconnected-(P7-Pad46)") (class "Default")
      (node (ref "P7") (pin "46") (pinfunction "46_46") (pintype "passive+no_connect"))
    )
    (net (code "140") (name "unconnected-(P7-Pad47)") (class "Default")
      (node (ref "P7") (pin "47") (pinfunction "47_47") (pintype "passive+no_connect"))
    )
    (net (code "141") (name "unconnected-(P7-Pad48)") (class "Default")
      (node (ref "P7") (pin "48") (pinfunction "48_48") (pintype "passive+no_connect"))
    )
    (net (code "142") (name "unconnected-(P7-Pad49)") (class "Default")
      (node (ref "P7") (pin "49") (pinfunction "49_49") (pintype "passive+no_connect"))
    )
    (net (code "143") (name "unconnected-(P7-Pad50)") (class "Default")
      (node (ref "P7") (pin "50") (pinfunction "50_50") (pintype "passive+no_connect"))
    )
    (net (code "144") (name "unconnected-(P7-Pad53)") (class "Default")
      (node (ref "P7") (pin "53") (pinfunction "53_53") (pintype "passive+no_connect"))
    )
    (net (code "145") (name "unconnected-(P7-Pad54)") (class "Default")
      (node (ref "P7") (pin "54") (pinfunction "54_54") (pintype "passive+no_connect"))
    )
    (net (code "146") (name "unconnected-(P7-Pad55)") (class "Default")
      (node (ref "P7") (pin "55") (pinfunction "55_55") (pintype "passive+no_connect"))
    )
    (net (code "147") (name "unconnected-(P7-Pad56)") (class "Default")
      (node (ref "P7") (pin "56") (pinfunction "56_56") (pintype "passive+no_connect"))
    )
    (net (code "148") (name "unconnected-(P7-Pad57)") (class "Default")
      (node (ref "P7") (pin "57") (pinfunction "57_57") (pintype "passive+no_connect"))
    )
    (net (code "149") (name "unconnected-(P7-Pad58)") (class "Default")
      (node (ref "P7") (pin "58") (pinfunction "58_58") (pintype "passive+no_connect"))
    )
    (net (code "150") (name "unconnected-(P7-Pad59)") (class "Default")
      (node (ref "P7") (pin "59") (pinfunction "59_59") (pintype "passive+no_connect"))
    )
    (net (code "151") (name "unconnected-(P7-Pad60)") (class "Default")
      (node (ref "P7") (pin "60") (pinfunction "60_60") (pintype "passive+no_connect"))
    )
    (net (code "152") (name "unconnected-(P8-Pad1)") (class "Default")
      (node (ref "P8") (pin "1") (pinfunction "1_1") (pintype "passive+no_connect"))
    )
    (net (code "153") (name "unconnected-(P8-Pad2)") (class "Default")
      (node (ref "P8") (pin "2") (pinfunction "2_2") (pintype "passive+no_connect"))
    )
    (net (code "154") (name "unconnected-(P8-Pad3)") (class "Default")
      (node (ref "P8") (pin "3") (pinfunction "3_3") (pintype "passive+no_connect"))
    )
    (net (code "155") (name "unconnected-(P8-Pad4)") (class "Default")
      (node (ref "P8") (pin "4") (pinfunction "4_4") (pintype "passive+no_connect"))
    )
    (net (code "156") (name "unconnected-(P8-Pad5)") (class "Default")
      (node (ref "P8") (pin "5") (pinfunction "5_5") (pintype "passive+no_connect"))
    )
    (net (code "157") (name "unconnected-(P8-Pad6)") (class "Default")
      (node (ref "P8") (pin "6") (pinfunction "6_6") (pintype "passive+no_connect"))
    )
    (net (code "158") (name "unconnected-(P8-Pad7)") (class "Default")
      (node (ref "P8") (pin "7") (pinfunction "7_7") (pintype "passive+no_connect"))
    )
    (net (code "159") (name "unconnected-(P8-Pad8)") (class "Default")
      (node (ref "P8") (pin "8") (pinfunction "8_8") (pintype "passive+no_connect"))
    )
    (net (code "160") (name "unconnected-(P8-Pad9)") (class "Default")
      (node (ref "P8") (pin "9") (pinfunction "9_9") (pintype "passive+no_connect"))
    )
    (net (code "161") (name "unconnected-(P8-Pad10)") (class "Default")
      (node (ref "P8") (pin "10") (pinfunction "10_10") (pintype "passive+no_connect"))
    )
    (net (code "162") (name "unconnected-(P8-Pad13)") (class "Default")
      (node (ref "P8") (pin "13") (pinfunction "13_13") (pintype "passive+no_connect"))
    )
    (net (code "163") (name "unconnected-(P8-Pad14)") (class "Default")
      (node (ref "P8") (pin "14") (pinfunction "14_14") (pintype "passive+no_connect"))
    )
    (net (code "164") (name "unconnected-(P8-Pad15)") (class "Default")
      (node (ref "P8") (pin "15") (pinfunction "15_15") (pintype "passive+no_connect"))
    )
    (net (code "165") (name "unconnected-(P8-Pad16)") (class "Default")
      (node (ref "P8") (pin "16") (pinfunction "16_16") (pintype "passive+no_connect"))
    )
    (net (code "166") (name "unconnected-(P8-Pad17)") (class "Default")
      (node (ref "P8") (pin "17") (pinfunction "17_17") (pintype "passive+no_connect"))
    )
    (net (code "167") (name "unconnected-(P8-Pad18)") (class "Default")
      (node (ref "P8") (pin "18") (pinfunction "18_18") (pintype "passive+no_connect"))
    )
    (net (code "168") (name "unconnected-(P8-Pad19)") (class "Default")
      (node (ref "P8") (pin "19") (pinfunction "19_19") (pintype "passive+no_connect"))
    )
    (net (code "169") (name "unconnected-(P8-Pad20)") (class "Default")
      (node (ref "P8") (pin "20") (pinfunction "20_20") (pintype "passive+no_connect"))
    )
    (net (code "170") (name "unconnected-(P8-Pad23)") (class "Default")
      (node (ref "P8") (pin "23") (pinfunction "23_23") (pintype "passive+no_connect"))
    )
    (net (code "171") (name "unconnected-(P8-Pad24)") (class "Default")
      (node (ref "P8") (pin "24") (pinfunction "24_24") (pintype "passive+no_connect"))
    )
    (net (code "172") (name "unconnected-(P8-Pad25)") (class "Default")
      (node (ref "P8") (pin "25") (pinfunction "25_25") (pintype "passive+no_connect"))
    )
    (net (code "173") (name "unconnected-(P8-Pad26)") (class "Default")
      (node (ref "P8") (pin "26") (pinfunction "26_26") (pintype "passive+no_connect"))
    )
    (net (code "174") (name "unconnected-(P8-Pad27)") (class "Default")
      (node (ref "P8") (pin "27") (pinfunction "27_27") (pintype "passive+no_connect"))
    )
    (net (code "175") (name "unconnected-(P8-Pad28)") (class "Default")
      (node (ref "P8") (pin "28") (pinfunction "28_28") (pintype "passive+no_connect"))
    )
    (net (code "176") (name "unconnected-(P8-Pad29)") (class "Default")
      (node (ref "P8") (pin "29") (pinfunction "29_29") (pintype "passive+no_connect"))
    )
    (net (code "177") (name "unconnected-(P8-Pad30)") (class "Default")
      (node (ref "P8") (pin "30") (pinfunction "30_30") (pintype "passive+no_connect"))
    )
    (net (code "178") (name "unconnected-(P8-Pad33)") (class "Default")
      (node (ref "P8") (pin "33") (pinfunction "33_33") (pintype "passive+no_connect"))
    )
    (net (code "179") (name "unconnected-(P8-Pad34)") (class "Default")
      (node (ref "P8") (pin "34") (pinfunction "34_34") (pintype "passive+no_connect"))
    )
    (net (code "180") (name "unconnected-(P8-Pad37)") (class "Default")
      (node (ref "P8") (pin "37") (pinfunction "37_37") (pintype "passive+no_connect"))
    )
    (net (code "181") (name "unconnected-(P8-Pad38)") (class "Default")
      (node (ref "P8") (pin "38") (pinfunction "38_38") (pintype "passive+no_connect"))
    )
    (net (code "182") (name "unconnected-(P8-Pad39)") (class "Default")
      (node (ref "P8") (pin "39") (pinfunction "39_39") (pintype "passive+no_connect"))
    )
    (net (code "183") (name "unconnected-(P8-Pad40)") (class "Default")
      (node (ref "P8") (pin "40") (pinfunction "40_40") (pintype "passive+no_connect"))
    )
    (net (code "184") (name "unconnected-(P8-Pad43)") (class "Default")
      (node (ref "P8") (pin "43") (pinfunction "43_43") (pintype "passive+no_connect"))
    )
    (net (code "185") (name "unconnected-(P8-Pad44)") (class "Default")
      (node (ref "P8") (pin "44") (pinfunction "44_44") (pintype "passive+no_connect"))
    )
    (net (code "186") (name "unconnected-(P8-Pad45)") (class "Default")
      (node (ref "P8") (pin "45") (pinfunction "45_45") (pintype "passive+no_connect"))
    )
    (net (code "187") (name "unconnected-(P8-Pad46)") (class "Default")
      (node (ref "P8") (pin "46") (pinfunction "46_46") (pintype "passive+no_connect"))
    )
    (net (code "188") (name "unconnected-(P8-Pad47)") (class "Default")
      (node (ref "P8") (pin "47") (pinfunction "47_47") (pintype "passive+no_connect"))
    )
    (net (code "189") (name "unconnected-(P8-Pad48)") (class "Default")
      (node (ref "P8") (pin "48") (pinfunction "48_48") (pintype "passive+no_connect"))
    )
    (net (code "190") (name "unconnected-(P8-Pad49)") (class "Default")
      (node (ref "P8") (pin "49") (pinfunction "49_49") (pintype "passive+no_connect"))
    )
    (net (code "191") (name "unconnected-(P8-Pad50)") (class "Default")
      (node (ref "P8") (pin "50") (pinfunction "50_50") (pintype "passive+no_connect"))
    )
    (net (code "192") (name "unconnected-(P8-Pad53)") (class "Default")
      (node (ref "P8") (pin "53") (pinfunction "53_53") (pintype "passive+no_connect"))
    )
    (net (code "193") (name "unconnected-(P8-Pad54)") (class "Default")
      (node (ref "P8") (pin "54") (pinfunction "54_54") (pintype "passive+no_connect"))
    )
    (net (code "194") (name "unconnected-(P8-Pad55)") (class "Default")
      (node (ref "P8") (pin "55") (pinfunction "55_55") (pintype "passive+no_connect"))
    )
    (net (code "195") (name "unconnected-(P8-Pad56)") (class "Default")
      (node (ref "P8") (pin "56") (pinfunction "56_56") (pintype "passive+no_connect"))
    )
    (net (code "196") (name "unconnected-(P8-Pad57)") (class "Default")
      (node (ref "P8") (pin "57") (pinfunction "57_57") (pintype "passive+no_connect"))
    )
    (net (code "197") (name "unconnected-(P8-Pad58)") (class "Default")
      (node (ref "P8") (pin "58") (pinfunction "58_58") (pintype "passive+no_connect"))
    )
    (net (code "198") (name "unconnected-(P8-Pad59)") (class "Default")
      (node (ref "P8") (pin "59") (pinfunction "59_59") (pintype "passive+no_connect"))
    )
    (net (code "199") (name "unconnected-(P8-Pad60)") (class "Default")
      (node (ref "P8") (pin "60") (pinfunction "60_60") (pintype "passive+no_connect"))
    )
  )
)
